# dynalo_v.net
KiCad netlist of a schematic drawn in EAGLE
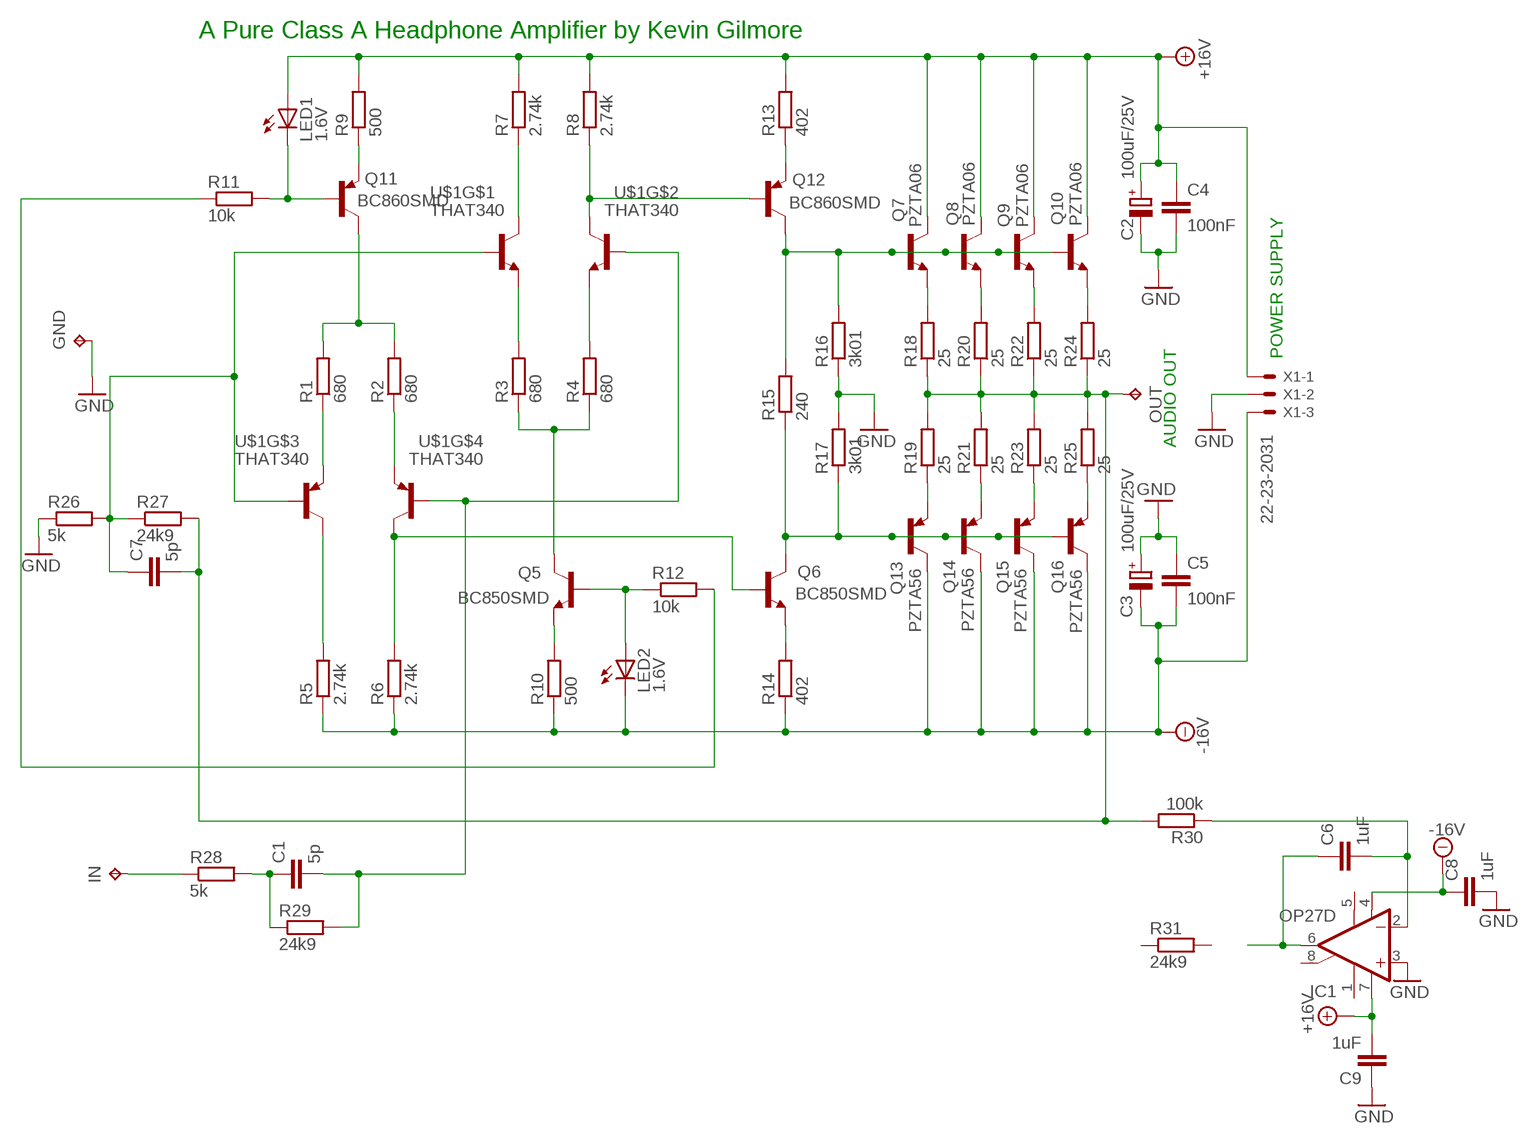
[diagram p0: schematic, sheet 1]

(export (version "E")
  (design (tool "Eeschema 10.0.6"))
  (components
    (comp (ref "C1")
      (value "5p")
      (footprint "eagle-import:C1206")
      (libsource (lib "eagle-import") (part "C-EUC1206"))
    )
    (comp (ref "C2")
      (value "100uF/25V")
      (footprint "eagle-import:E3,5-8")
      (libsource (lib "eagle-import") (part "CPOL-EUE3.5-8"))
    )
    (comp (ref "C3")
      (value "100uF/25V")
      (footprint "eagle-import:E3,5-8")
      (libsource (lib "eagle-import") (part "CPOL-EUE3.5-8"))
    )
    (comp (ref "C4")
      (value "100nF")
      (footprint "eagle-import:C050-035X075")
      (libsource (lib "eagle-import") (part "rcl_C-EU050-035X075"))
    )
    (comp (ref "C5")
      (value "100nF")
      (footprint "eagle-import:C050-035X075")
      (libsource (lib "eagle-import") (part "rcl_C-EU050-035X075"))
    )
    (comp (ref "C6")
      (value "1uF")
      (footprint "eagle-import:C1206")
      (libsource (lib "eagle-import") (part "C-EUC1206"))
    )
    (comp (ref "C7")
      (value "5p")
      (footprint "eagle-import:C1206")
      (libsource (lib "eagle-import") (part "C-EUC1206"))
    )
    (comp (ref "C8")
      (value "1uF")
      (footprint "eagle-import:C1206")
      (libsource (lib "eagle-import") (part "C-EUC1206"))
    )
    (comp (ref "C9")
      (value "1uF")
      (footprint "eagle-import:C1206")
      (libsource (lib "eagle-import") (part "C-EUC1206"))
    )
    (comp (ref "GND")
      (value "TPPAD1-20")
      (footprint "eagle-import:P1-20")
      (libsource (lib "eagle-import") (part "TPPAD1-20"))
    )
    (comp (ref "IC1")
      (value "OP27D")
      (footprint "eagle-import:SO08")
      (libsource (lib "eagle-import") (part "OP27D"))
    )
    (comp (ref "IN")
      (value "TPPAD1-20")
      (footprint "eagle-import:P1-20")
      (libsource (lib "eagle-import") (part "TPPAD1-20"))
    )
    (comp (ref "LED1")
      (value "1.6V")
      (footprint "eagle-import:CHIPLED_1206")
      (libsource (lib "eagle-import") (part "LEDCHIPLED_1206"))
    )
    (comp (ref "LED2")
      (value "1.6V")
      (footprint "eagle-import:CHIPLED_1206")
      (libsource (lib "eagle-import") (part "LEDCHIPLED_1206"))
    )
    (comp (ref "OUT")
      (value "TPPAD1-20")
      (footprint "eagle-import:P1-20")
      (libsource (lib "eagle-import") (part "TPPAD1-20"))
    )
    (comp (ref "Q5")
      (value "BC850SMD")
      (footprint "eagle-import:SOT23-BEC")
      (libsource (lib "eagle-import") (part "BC850SMD"))
    )
    (comp (ref "Q6")
      (value "BC850SMD")
      (footprint "eagle-import:SOT23-BEC")
      (libsource (lib "eagle-import") (part "BC850SMD"))
    )
    (comp (ref "Q7")
      (value "PZTA06")
      (footprint "eagle-import:SOT223R_INFINEON")
      (libsource (lib "eagle-import") (part "PZTA06"))
    )
    (comp (ref "Q8")
      (value "PZTA06")
      (footprint "eagle-import:SOT223R_INFINEON")
      (libsource (lib "eagle-import") (part "PZTA06"))
    )
    (comp (ref "Q9")
      (value "PZTA06")
      (footprint "eagle-import:SOT223R_INFINEON")
      (libsource (lib "eagle-import") (part "PZTA06"))
    )
    (comp (ref "Q10")
      (value "PZTA06")
      (footprint "eagle-import:SOT223R_INFINEON")
      (libsource (lib "eagle-import") (part "PZTA06"))
    )
    (comp (ref "Q11")
      (value "BC860SMD")
      (footprint "eagle-import:SOT23-BEC")
      (libsource (lib "eagle-import") (part "BC860SMDC"))
    )
    (comp (ref "Q12")
      (value "BC860SMD")
      (footprint "eagle-import:SOT23-BEC")
      (libsource (lib "eagle-import") (part "BC860SMDC"))
    )
    (comp (ref "Q13")
      (value "PZTA56")
      (footprint "eagle-import:SOT223R_INFINEON")
      (libsource (lib "eagle-import") (part "PZTA56"))
    )
    (comp (ref "Q14")
      (value "PZTA56")
      (footprint "eagle-import:SOT223R_INFINEON")
      (libsource (lib "eagle-import") (part "PZTA56"))
    )
    (comp (ref "Q15")
      (value "PZTA56")
      (footprint "eagle-import:SOT223R_INFINEON")
      (libsource (lib "eagle-import") (part "PZTA56"))
    )
    (comp (ref "Q16")
      (value "PZTA56")
      (footprint "eagle-import:SOT223R_INFINEON")
      (libsource (lib "eagle-import") (part "PZTA56"))
    )
    (comp (ref "R1")
      (value "680")
      (footprint "eagle-import:MINI_MELF-0204W")
      (libsource (lib "eagle-import") (part "R-EU_MELF0204W"))
    )
    (comp (ref "R2")
      (value "680")
      (footprint "eagle-import:MINI_MELF-0204W")
      (libsource (lib "eagle-import") (part "R-EU_MELF0204W"))
    )
    (comp (ref "R3")
      (value "680")
      (footprint "eagle-import:MINI_MELF-0204W")
      (libsource (lib "eagle-import") (part "R-EU_MELF0204W"))
    )
    (comp (ref "R4")
      (value "680")
      (footprint "eagle-import:MINI_MELF-0204W")
      (libsource (lib "eagle-import") (part "R-EU_MELF0204W"))
    )
    (comp (ref "R5")
      (value "2.74k")
      (footprint "eagle-import:MINI_MELF-0204W")
      (libsource (lib "eagle-import") (part "R-EU_MELF0204W"))
    )
    (comp (ref "R6")
      (value "2.74k")
      (footprint "eagle-import:MINI_MELF-0204W")
      (libsource (lib "eagle-import") (part "R-EU_MELF0204W"))
    )
    (comp (ref "R7")
      (value "2.74k")
      (footprint "eagle-import:MINI_MELF-0204W")
      (libsource (lib "eagle-import") (part "R-EU_MELF0204W"))
    )
    (comp (ref "R8")
      (value "2.74k")
      (footprint "eagle-import:MINI_MELF-0204W")
      (libsource (lib "eagle-import") (part "R-EU_MELF0204W"))
    )
    (comp (ref "R9")
      (value "500")
      (footprint "eagle-import:MINI_MELF-0204W")
      (libsource (lib "eagle-import") (part "R-EU_MELF0204W"))
    )
    (comp (ref "R10")
      (value "500")
      (footprint "eagle-import:MINI_MELF-0204W")
      (libsource (lib "eagle-import") (part "R-EU_MELF0204W"))
    )
    (comp (ref "R11")
      (value "10k")
      (footprint "eagle-import:MINI_MELF-0204W")
      (libsource (lib "eagle-import") (part "R-EU_MELF0204W"))
    )
    (comp (ref "R12")
      (value "10k")
      (footprint "eagle-import:MINI_MELF-0204W")
      (libsource (lib "eagle-import") (part "R-EU_MELF0204W"))
    )
    (comp (ref "R13")
      (value "402")
      (footprint "eagle-import:MINI_MELF-0204W")
      (libsource (lib "eagle-import") (part "R-EU_MELF0204W"))
    )
    (comp (ref "R14")
      (value "402")
      (footprint "eagle-import:MINI_MELF-0204W")
      (libsource (lib "eagle-import") (part "R-EU_MELF0204W"))
    )
    (comp (ref "R15")
      (value "240")
      (footprint "eagle-import:MINI_MELF-0204W")
      (libsource (lib "eagle-import") (part "R-EU_MELF0204W"))
    )
    (comp (ref "R16")
      (value "3k01")
      (footprint "eagle-import:MINI_MELF-0204W")
      (libsource (lib "eagle-import") (part "R-EU_MELF0204W"))
    )
    (comp (ref "R17")
      (value "3k01")
      (footprint "eagle-import:MINI_MELF-0204W")
      (libsource (lib "eagle-import") (part "R-EU_MELF0204W"))
    )
    (comp (ref "R18")
      (value "25")
      (footprint "eagle-import:MINI_MELF-0204W")
      (libsource (lib "eagle-import") (part "R-EU_MELF0204W"))
    )
    (comp (ref "R19")
      (value "25")
      (footprint "eagle-import:MINI_MELF-0204W")
      (libsource (lib "eagle-import") (part "R-EU_MELF0204W"))
    )
    (comp (ref "R20")
      (value "25")
      (footprint "eagle-import:MINI_MELF-0204W")
      (libsource (lib "eagle-import") (part "R-EU_MELF0204W"))
    )
    (comp (ref "R21")
      (value "25")
      (footprint "eagle-import:MINI_MELF-0204W")
      (libsource (lib "eagle-import") (part "R-EU_MELF0204W"))
    )
    (comp (ref "R22")
      (value "25")
      (footprint "eagle-import:MINI_MELF-0204W")
      (libsource (lib "eagle-import") (part "R-EU_MELF0204W"))
    )
    (comp (ref "R23")
      (value "25")
      (footprint "eagle-import:MINI_MELF-0204W")
      (libsource (lib "eagle-import") (part "R-EU_MELF0204W"))
    )
    (comp (ref "R24")
      (value "25")
      (footprint "eagle-import:MINI_MELF-0204W")
      (libsource (lib "eagle-import") (part "R-EU_MELF0204W"))
    )
    (comp (ref "R25")
      (value "25")
      (footprint "eagle-import:MINI_MELF-0204W")
      (libsource (lib "eagle-import") (part "R-EU_MELF0204W"))
    )
    (comp (ref "R26")
      (value "5k")
      (footprint "eagle-import:MINI_MELF-0204W")
      (libsource (lib "eagle-import") (part "R-EU_MELF0204W"))
    )
    (comp (ref "R27")
      (value "24k9")
      (footprint "eagle-import:MINI_MELF-0204W")
      (libsource (lib "eagle-import") (part "R-EU_MELF0204W"))
    )
    (comp (ref "R28")
      (value "5k")
      (footprint "eagle-import:MINI_MELF-0204W")
      (libsource (lib "eagle-import") (part "R-EU_MELF0204W"))
    )
    (comp (ref "R29")
      (value "24k9")
      (footprint "eagle-import:MINI_MELF-0204W")
      (libsource (lib "eagle-import") (part "R-EU_MELF0204W"))
    )
    (comp (ref "R30")
      (value "100k")
      (footprint "eagle-import:MINI_MELF-0204W")
      (libsource (lib "eagle-import") (part "R-EU_MELF0204W"))
    )
    (comp (ref "R31")
      (value "24k9")
      (footprint "eagle-import:MINI_MELF-0204W")
      (libsource (lib "eagle-import") (part "R-EU_MELF0204W"))
    )
    (comp (ref "U$1")
      (value "THAT340")
      (footprint "eagle-import:DIP254P762X510-14")
      (libsource (lib "eagle-import") (part "THAT340"))
    )
    (comp (ref "X1")
      (value "22-23-2031")
      (footprint "eagle-import:22-23-2031")
      (fields (field (name "MF") "MOLEX"))
      (libsource (lib "eagle-import") (part "22-23-2031"))
    )
  )
  (nets
    (net (code "1") (name "+16V") (class "Default")
      (node (ref "C2") (pin "+") (pinfunction "+_+") (pintype "passive"))
      (node (ref "C4") (pin "1") (pinfunction "1_1") (pintype "passive"))
      (node (ref "C9") (pin "2") (pinfunction "2_2") (pintype "passive"))
      (node (ref "IC1") (pin "7") (pinfunction "V+_7") (pintype "power_in"))
      (node (ref "LED1") (pin "A") (pinfunction "A_A") (pintype "passive"))
      (node (ref "Q10") (pin "2") (pinfunction "C_2") (pintype "passive"))
      (node (ref "Q10") (pin "4") (pinfunction "C_4") (pintype "passive"))
      (node (ref "Q7") (pin "2") (pinfunction "C_2") (pintype "passive"))
      (node (ref "Q7") (pin "4") (pinfunction "C_4") (pintype "passive"))
      (node (ref "Q8") (pin "2") (pinfunction "C_2") (pintype "passive"))
      (node (ref "Q8") (pin "4") (pinfunction "C_4") (pintype "passive"))
      (node (ref "Q9") (pin "2") (pinfunction "C_2") (pintype "passive"))
      (node (ref "Q9") (pin "4") (pinfunction "C_4") (pintype "passive"))
      (node (ref "R13") (pin "2") (pinfunction "2_2") (pintype "passive"))
      (node (ref "R7") (pin "2") (pinfunction "2_2") (pintype "passive"))
      (node (ref "R8") (pin "2") (pinfunction "2_2") (pintype "passive"))
      (node (ref "R9") (pin "2") (pinfunction "2_2") (pintype "passive"))
      (node (ref "X1") (pin "1") (pinfunction "S_1") (pintype "passive"))
    )
    (net (code "2") (name "-16V") (class "Default")
      (node (ref "C3") (pin "-") (pinfunction "-_-") (pintype "passive"))
      (node (ref "C5") (pin "2") (pinfunction "2_2") (pintype "passive"))
      (node (ref "C8") (pin "1") (pinfunction "1_1") (pintype "passive"))
      (node (ref "IC1") (pin "4") (pinfunction "V-_4") (pintype "power_in"))
      (node (ref "LED2") (pin "C") (pinfunction "C_C") (pintype "passive"))
      (node (ref "Q13") (pin "2") (pinfunction "C_2") (pintype "passive"))
      (node (ref "Q13") (pin "4") (pinfunction "C_4") (pintype "passive"))
      (node (ref "Q14") (pin "2") (pinfunction "C_2") (pintype "passive"))
      (node (ref "Q14") (pin "4") (pinfunction "C_4") (pintype "passive"))
      (node (ref "Q15") (pin "2") (pinfunction "C_2") (pintype "passive"))
      (node (ref "Q15") (pin "4") (pinfunction "C_4") (pintype "passive"))
      (node (ref "Q16") (pin "2") (pinfunction "C_2") (pintype "passive"))
      (node (ref "Q16") (pin "4") (pinfunction "C_4") (pintype "passive"))
      (node (ref "R10") (pin "1") (pinfunction "1_1") (pintype "passive"))
      (node (ref "R14") (pin "1") (pinfunction "1_1") (pintype "passive"))
      (node (ref "R5") (pin "1") (pinfunction "1_1") (pintype "passive"))
      (node (ref "R6") (pin "1") (pinfunction "1_1") (pintype "passive"))
      (node (ref "X1") (pin "3") (pinfunction "S_3") (pintype "passive"))
    )
    (net (code "3") (name "GND") (class "Default")
      (node (ref "C2") (pin "-") (pinfunction "-_-") (pintype "passive"))
      (node (ref "C3") (pin "+") (pinfunction "+_+") (pintype "passive"))
      (node (ref "C4") (pin "2") (pinfunction "2_2") (pintype "passive"))
      (node (ref "C5") (pin "1") (pinfunction "1_1") (pintype "passive"))
      (node (ref "C8") (pin "2") (pinfunction "2_2") (pintype "passive"))
      (node (ref "C9") (pin "1") (pinfunction "1_1") (pintype "passive"))
      (node (ref "GND") (pin "TP") (pinfunction "TP_TP") (pintype "input"))
      (node (ref "IC1") (pin "3") (pinfunction "+IN_3") (pintype "input"))
      (node (ref "R16") (pin "1") (pinfunction "1_1") (pintype "passive"))
      (node (ref "R17") (pin "2") (pinfunction "2_2") (pintype "passive"))
      (node (ref "R26") (pin "1") (pinfunction "1_1") (pintype "passive"))
      (node (ref "X1") (pin "2") (pinfunction "S_2") (pintype "passive"))
    )
    (net (code "4") (name "Net-(C1-Pad1)") (class "Default")
      (node (ref "C1") (pin "1") (pinfunction "1_1") (pintype "passive"))
      (node (ref "R28") (pin "2") (pinfunction "2_2") (pintype "passive"))
      (node (ref "R29") (pin "1") (pinfunction "1_1") (pintype "passive"))
    )
    (net (code "5") (name "Net-(C7-Pad2)") (class "Default")
      (node (ref "C7") (pin "2") (pinfunction "2_2") (pintype "passive"))
      (node (ref "OUT") (pin "TP") (pinfunction "TP_TP") (pintype "input"))
      (node (ref "R18") (pin "1") (pinfunction "1_1") (pintype "passive"))
      (node (ref "R19") (pin "2") (pinfunction "2_2") (pintype "passive"))
      (node (ref "R20") (pin "1") (pinfunction "1_1") (pintype "passive"))
      (node (ref "R21") (pin "2") (pinfunction "2_2") (pintype "passive"))
      (node (ref "R22") (pin "1") (pinfunction "1_1") (pintype "passive"))
      (node (ref "R23") (pin "2") (pinfunction "2_2") (pintype "passive"))
      (node (ref "R24") (pin "1") (pinfunction "1_1") (pintype "passive"))
      (node (ref "R25") (pin "2") (pinfunction "2_2") (pintype "passive"))
      (node (ref "R27") (pin "2") (pinfunction "2_2") (pintype "passive"))
      (node (ref "R30") (pin "2") (pinfunction "2_2") (pintype "passive"))
    )
    (net (code "6") (name "Net-(IC1--IN)") (class "Default")
      (node (ref "C6") (pin "2") (pinfunction "2_2") (pintype "passive"))
      (node (ref "IC1") (pin "2") (pinfunction "-IN_2") (pintype "input"))
      (node (ref "R30") (pin "1") (pinfunction "1_1") (pintype "passive"))
    )
    (net (code "7") (name "Net-(IC1-OUT)") (class "Default")
      (node (ref "C6") (pin "1") (pinfunction "1_1") (pintype "passive"))
      (node (ref "IC1") (pin "6") (pinfunction "OUT_6") (pintype "output"))
    )
    (net (code "8") (name "Net-(IN-PadTP)") (class "Default")
      (node (ref "IN") (pin "TP") (pinfunction "TP_TP") (pintype "input"))
      (node (ref "R28") (pin "1") (pinfunction "1_1") (pintype "passive"))
    )
    (net (code "9") (name "Net-(LED1-PadC)") (class "Default")
      (node (ref "LED1") (pin "C") (pinfunction "C_C") (pintype "passive"))
      (node (ref "Q11") (pin "B") (pinfunction "B_B") (pintype "passive"))
      (node (ref "R11") (pin "2") (pinfunction "2_2") (pintype "passive"))
    )
    (net (code "10") (name "Net-(LED2-PadA)") (class "Default")
      (node (ref "LED2") (pin "A") (pinfunction "A_A") (pintype "passive"))
      (node (ref "Q5") (pin "B") (pinfunction "B_B") (pintype "passive"))
      (node (ref "R12") (pin "1") (pinfunction "1_1") (pintype "passive"))
    )
    (net (code "11") (name "Net-(Q5-PadC)") (class "Default")
      (node (ref "Q5") (pin "C") (pinfunction "C_C") (pintype "passive"))
      (node (ref "R3") (pin "1") (pinfunction "1_1") (pintype "passive"))
      (node (ref "R4") (pin "1") (pinfunction "1_1") (pintype "passive"))
    )
    (net (code "12") (name "Net-(Q5-PadE)") (class "Default")
      (node (ref "Q5") (pin "E") (pinfunction "E_E") (pintype "passive"))
      (node (ref "R10") (pin "2") (pinfunction "2_2") (pintype "passive"))
    )
    (net (code "13") (name "Net-(Q6-PadE)") (class "Default")
      (node (ref "Q6") (pin "E") (pinfunction "E_E") (pintype "passive"))
      (node (ref "R14") (pin "2") (pinfunction "2_2") (pintype "passive"))
    )
    (net (code "14") (name "Net-(Q7-E)") (class "Default")
      (node (ref "Q7") (pin "3") (pinfunction "E_3") (pintype "passive"))
      (node (ref "R18") (pin "2") (pinfunction "2_2") (pintype "passive"))
    )
    (net (code "15") (name "Net-(Q8-E)") (class "Default")
      (node (ref "Q8") (pin "3") (pinfunction "E_3") (pintype "passive"))
      (node (ref "R20") (pin "2") (pinfunction "2_2") (pintype "passive"))
    )
    (net (code "16") (name "Net-(Q9-E)") (class "Default")
      (node (ref "Q9") (pin "3") (pinfunction "E_3") (pintype "passive"))
      (node (ref "R22") (pin "2") (pinfunction "2_2") (pintype "passive"))
    )
    (net (code "17") (name "Net-(Q10-B)") (class "Default")
      (node (ref "Q10") (pin "1") (pinfunction "B_1") (pintype "passive"))
      (node (ref "Q12") (pin "C") (pinfunction "C_C") (pintype "passive"))
      (node (ref "Q7") (pin "1") (pinfunction "B_1") (pintype "passive"))
      (node (ref "Q8") (pin "1") (pinfunction "B_1") (pintype "passive"))
      (node (ref "Q9") (pin "1") (pinfunction "B_1") (pintype "passive"))
      (node (ref "R15") (pin "2") (pinfunction "2_2") (pintype "passive"))
      (node (ref "R16") (pin "2") (pinfunction "2_2") (pintype "passive"))
    )
    (net (code "18") (name "Net-(Q10-E)") (class "Default")
      (node (ref "Q10") (pin "3") (pinfunction "E_3") (pintype "passive"))
      (node (ref "R24") (pin "2") (pinfunction "2_2") (pintype "passive"))
    )
    (net (code "19") (name "Net-(Q11-PadC)") (class "Default")
      (node (ref "Q11") (pin "C") (pinfunction "C_C") (pintype "passive"))
      (node (ref "R1") (pin "2") (pinfunction "2_2") (pintype "passive"))
      (node (ref "R2") (pin "2") (pinfunction "2_2") (pintype "passive"))
    )
    (net (code "20") (name "Net-(Q11-PadE)") (class "Default")
      (node (ref "Q11") (pin "E") (pinfunction "E_E") (pintype "passive"))
      (node (ref "R9") (pin "1") (pinfunction "1_1") (pintype "passive"))
    )
    (net (code "21") (name "Net-(Q12-PadE)") (class "Default")
      (node (ref "Q12") (pin "E") (pinfunction "E_E") (pintype "passive"))
      (node (ref "R13") (pin "1") (pinfunction "1_1") (pintype "passive"))
    )
    (net (code "22") (name "Net-(Q13-B)") (class "Default")
      (node (ref "Q13") (pin "1") (pinfunction "B_1") (pintype "passive"))
      (node (ref "Q14") (pin "1") (pinfunction "B_1") (pintype "passive"))
      (node (ref "Q15") (pin "1") (pinfunction "B_1") (pintype "passive"))
      (node (ref "Q16") (pin "1") (pinfunction "B_1") (pintype "passive"))
      (node (ref "Q6") (pin "C") (pinfunction "C_C") (pintype "passive"))
      (node (ref "R15") (pin "1") (pinfunction "1_1") (pintype "passive"))
      (node (ref "R17") (pin "1") (pinfunction "1_1") (pintype "passive"))
    )
    (net (code "23") (name "Net-(Q13-E)") (class "Default")
      (node (ref "Q13") (pin "3") (pinfunction "E_3") (pintype "passive"))
      (node (ref "R19") (pin "1") (pinfunction "1_1") (pintype "passive"))
    )
    (net (code "24") (name "Net-(Q14-E)") (class "Default")
      (node (ref "Q14") (pin "3") (pinfunction "E_3") (pintype "passive"))
      (node (ref "R21") (pin "1") (pinfunction "1_1") (pintype "passive"))
    )
    (net (code "25") (name "Net-(Q15-E)") (class "Default")
      (node (ref "Q15") (pin "3") (pinfunction "E_3") (pintype "passive"))
      (node (ref "R23") (pin "1") (pinfunction "1_1") (pintype "passive"))
    )
    (net (code "26") (name "Net-(Q16-E)") (class "Default")
      (node (ref "Q16") (pin "3") (pinfunction "E_3") (pintype "passive"))
      (node (ref "R25") (pin "1") (pinfunction "1_1") (pintype "passive"))
    )
    (net (code "27") (name "Net-(R11-Pad1)") (class "Default")
      (node (ref "R11") (pin "1") (pinfunction "1_1") (pintype "passive"))
      (node (ref "R12") (pin "2") (pinfunction "2_2") (pintype "passive"))
    )
    (net (code "28") (name "Net-(U$1A-B)") (class "Default")
      (node (ref "C7") (pin "1") (pinfunction "1_1") (pintype "passive"))
      (node (ref "R26") (pin "2") (pinfunction "2_2") (pintype "passive"))
      (node (ref "R27") (pin "1") (pinfunction "1_1") (pintype "passive"))
      (node (ref "U$1") (pin "2") (pinfunction "B_2") (pintype "passive"))
      (node (ref "U$1") (pin "6") (pinfunction "B_6") (pintype "passive"))
    )
    (net (code "29") (name "Net-(U$1A-C)") (class "Default")
      (node (ref "R7") (pin "1") (pinfunction "1_1") (pintype "passive"))
      (node (ref "U$1") (pin "1") (pinfunction "C_1") (pintype "passive"))
    )
    (net (code "30") (name "Net-(U$1A-E)") (class "Default")
      (node (ref "R3") (pin "2") (pinfunction "2_2") (pintype "passive"))
      (node (ref "U$1") (pin "3") (pinfunction "E_3") (pintype "passive"))
    )
    (net (code "31") (name "Net-(U$1B-B)") (class "Default")
      (node (ref "C1") (pin "2") (pinfunction "2_2") (pintype "passive"))
      (node (ref "R29") (pin "2") (pinfunction "2_2") (pintype "passive"))
      (node (ref "U$1") (pin "13") (pinfunction "B_13") (pintype "passive"))
      (node (ref "U$1") (pin "9") (pinfunction "B_9") (pintype "passive"))
    )
    (net (code "32") (name "Net-(U$1B-C)") (class "Default")
      (node (ref "Q12") (pin "B") (pinfunction "B_B") (pintype "passive"))
      (node (ref "R8") (pin "1") (pinfunction "1_1") (pintype "passive"))
      (node (ref "U$1") (pin "14") (pinfunction "C_14") (pintype "passive"))
    )
    (net (code "33") (name "Net-(U$1B-E)") (class "Default")
      (node (ref "R4") (pin "2") (pinfunction "2_2") (pintype "passive"))
      (node (ref "U$1") (pin "12") (pinfunction "E_12") (pintype "passive"))
    )
    (net (code "34") (name "Net-(U$1C-C)") (class "Default")
      (node (ref "R5") (pin "2") (pinfunction "2_2") (pintype "passive"))
      (node (ref "U$1") (pin "7") (pinfunction "C_7") (pintype "passive"))
    )
    (net (code "35") (name "Net-(U$1C-E)") (class "Default")
      (node (ref "R1") (pin "1") (pinfunction "1_1") (pintype "passive"))
      (node (ref "U$1") (pin "5") (pinfunction "E_5") (pintype "passive"))
    )
    (net (code "36") (name "Net-(U$1D-C)") (class "Default")
      (node (ref "Q6") (pin "B") (pinfunction "B_B") (pintype "passive"))
      (node (ref "R6") (pin "2") (pinfunction "2_2") (pintype "passive"))
      (node (ref "U$1") (pin "8") (pinfunction "C_8") (pintype "passive"))
    )
    (net (code "37") (name "Net-(U$1D-E)") (class "Default")
      (node (ref "R2") (pin "1") (pinfunction "1_1") (pintype "passive"))
      (node (ref "U$1") (pin "10") (pinfunction "E_10") (pintype "passive"))
    )
    (net (code "38") (name "unconnected-(IC1-ON1-Pad1)") (class "Default")
      (node (ref "IC1") (pin "1") (pinfunction "ON1_1") (pintype "passive"))
    )
    (net (code "39") (name "unconnected-(IC1-ON2-Pad8)") (class "Default")
      (node (ref "IC1") (pin "8") (pinfunction "ON2_8") (pintype "passive"))
    )
    (net (code "40") (name "unconnected-(IC1-OPT-Pad5)") (class "Default")
      (node (ref "IC1") (pin "5") (pinfunction "OPT_5") (pintype "passive"))
    )
    (net (code "41") (name "unconnected-(R31-Pad1)") (class "Default")
      (node (ref "R31") (pin "1") (pinfunction "1_1") (pintype "passive"))
    )
    (net (code "42") (name "unconnected-(R31-Pad2)") (class "Default")
      (node (ref "R31") (pin "2") (pinfunction "2_2") (pintype "passive"))
    )
  )
)
